# 6xLED_Panel.net
KiCad netlist of a schematic drawn in EAGLE
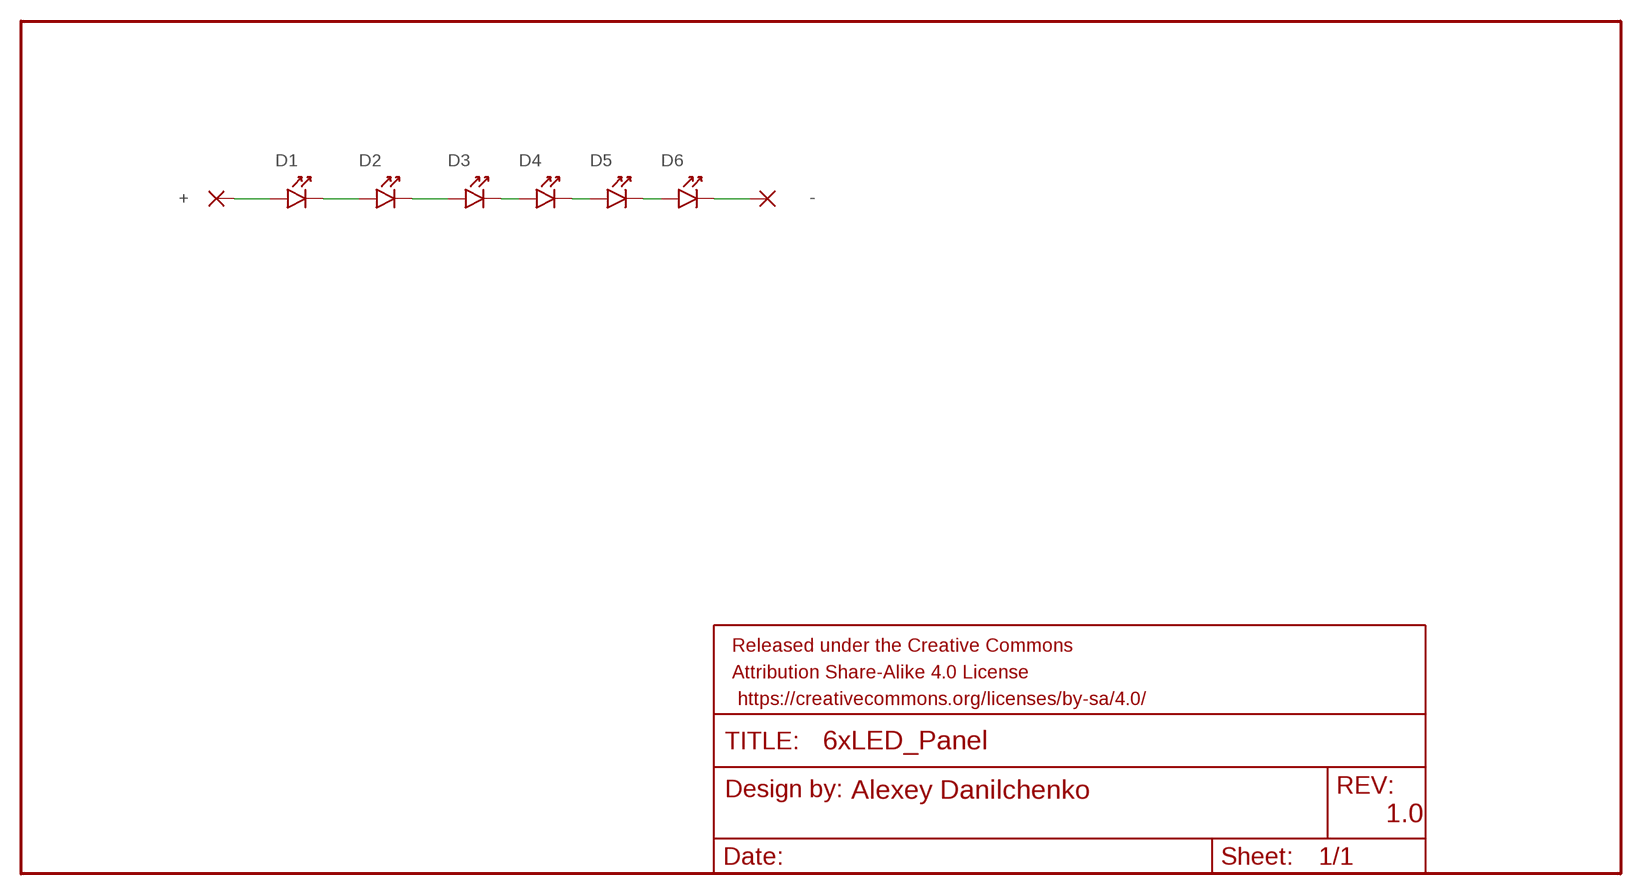
[diagram p0: schematic, sheet 1]

(export (version "E")
  (design (tool "Eeschema 10.0.6"))
  (components
    (comp (ref "+")
      (value "WIREPAD1,6/0,9")
      (footprint "eagle-import:2,15_1,0")
      (libsource (lib "eagle-import") (part "2,15/1,0"))
    )
    (comp (ref "-")
      (value "2,15/1,0")
      (footprint "eagle-import:2,15_1,0")
      (libsource (lib "eagle-import") (part "2,15/1,0"))
    )
    (comp (ref "D1")
      (value "YUJI_2835_SMD")
      (footprint "eagle-import:2835_SMD")
      (libsource (lib "eagle-import") (part "YUJI_2835_SMD"))
    )
    (comp (ref "D2")
      (value "YUJI_2835_SMD")
      (footprint "eagle-import:2835_SMD")
      (libsource (lib "eagle-import") (part "YUJI_2835_SMD"))
    )
    (comp (ref "D3")
      (value "YUJI_2835_SMD")
      (footprint "eagle-import:2835_SMD")
      (libsource (lib "eagle-import") (part "YUJI_2835_SMD"))
    )
    (comp (ref "D4")
      (value "YUJI_2835_SMD")
      (footprint "eagle-import:2835_SMD")
      (libsource (lib "eagle-import") (part "YUJI_2835_SMD"))
    )
    (comp (ref "D5")
      (value "YUJI_2835_SMD")
      (footprint "eagle-import:2835_SMD")
      (libsource (lib "eagle-import") (part "YUJI_2835_SMD"))
    )
    (comp (ref "D6")
      (value "YUJI_2835_SMD")
      (footprint "eagle-import:2835_SMD")
      (libsource (lib "eagle-import") (part "YUJI_2835_SMD"))
    )
    (comp (ref "FRAME1")
      (value "FRAME-LEDGER")
      (footprint "eagle-import:CREATIVE_COMMONS")
      (fields (field (name "AUTHOR") "Alexey Danilchenko") (field (name "VER") "1.0"))
      (libsource (lib "eagle-import") (part "FRAME-LEDGER"))
    )
  )
  (nets
    (net (code "1") (name "Net-(+-P)") (class "Default")
      (node (ref "+") (pin "1") (pinfunction "P_1") (pintype "passive"))
      (node (ref "D1") (pin "ANODE") (pinfunction "ANODE_ANODE") (pintype "bidirectional"))
    )
    (net (code "2") (name "Net-(--P)") (class "Default")
      (node (ref "-") (pin "1") (pinfunction "P_1") (pintype "passive"))
      (node (ref "D6") (pin "CATHODE") (pinfunction "CATHODE_CATHODE") (pintype "bidirectional"))
    )
    (net (code "3") (name "Net-(D1-PadCATHODE)") (class "Default")
      (node (ref "D1") (pin "CATHODE") (pinfunction "CATHODE_CATHODE") (pintype "bidirectional"))
      (node (ref "D2") (pin "ANODE") (pinfunction "ANODE_ANODE") (pintype "bidirectional"))
    )
    (net (code "4") (name "Net-(D2-PadCATHODE)") (class "Default")
      (node (ref "D2") (pin "CATHODE") (pinfunction "CATHODE_CATHODE") (pintype "bidirectional"))
      (node (ref "D3") (pin "ANODE") (pinfunction "ANODE_ANODE") (pintype "bidirectional"))
    )
    (net (code "5") (name "Net-(D3-PadCATHODE)") (class "Default")
      (node (ref "D3") (pin "CATHODE") (pinfunction "CATHODE_CATHODE") (pintype "bidirectional"))
      (node (ref "D4") (pin "ANODE") (pinfunction "ANODE_ANODE") (pintype "bidirectional"))
    )
    (net (code "6") (name "Net-(D4-PadCATHODE)") (class "Default")
      (node (ref "D4") (pin "CATHODE") (pinfunction "CATHODE_CATHODE") (pintype "bidirectional"))
      (node (ref "D5") (pin "ANODE") (pinfunction "ANODE_ANODE") (pintype "bidirectional"))
    )
    (net (code "7") (name "Net-(D5-PadCATHODE)") (class "Default")
      (node (ref "D5") (pin "CATHODE") (pinfunction "CATHODE_CATHODE") (pintype "bidirectional"))
      (node (ref "D6") (pin "ANODE") (pinfunction "ANODE_ANODE") (pintype "bidirectional"))
    )
  )
)
